# docking-control.net
KiCad netlist of a schematic drawn in Altium Designer
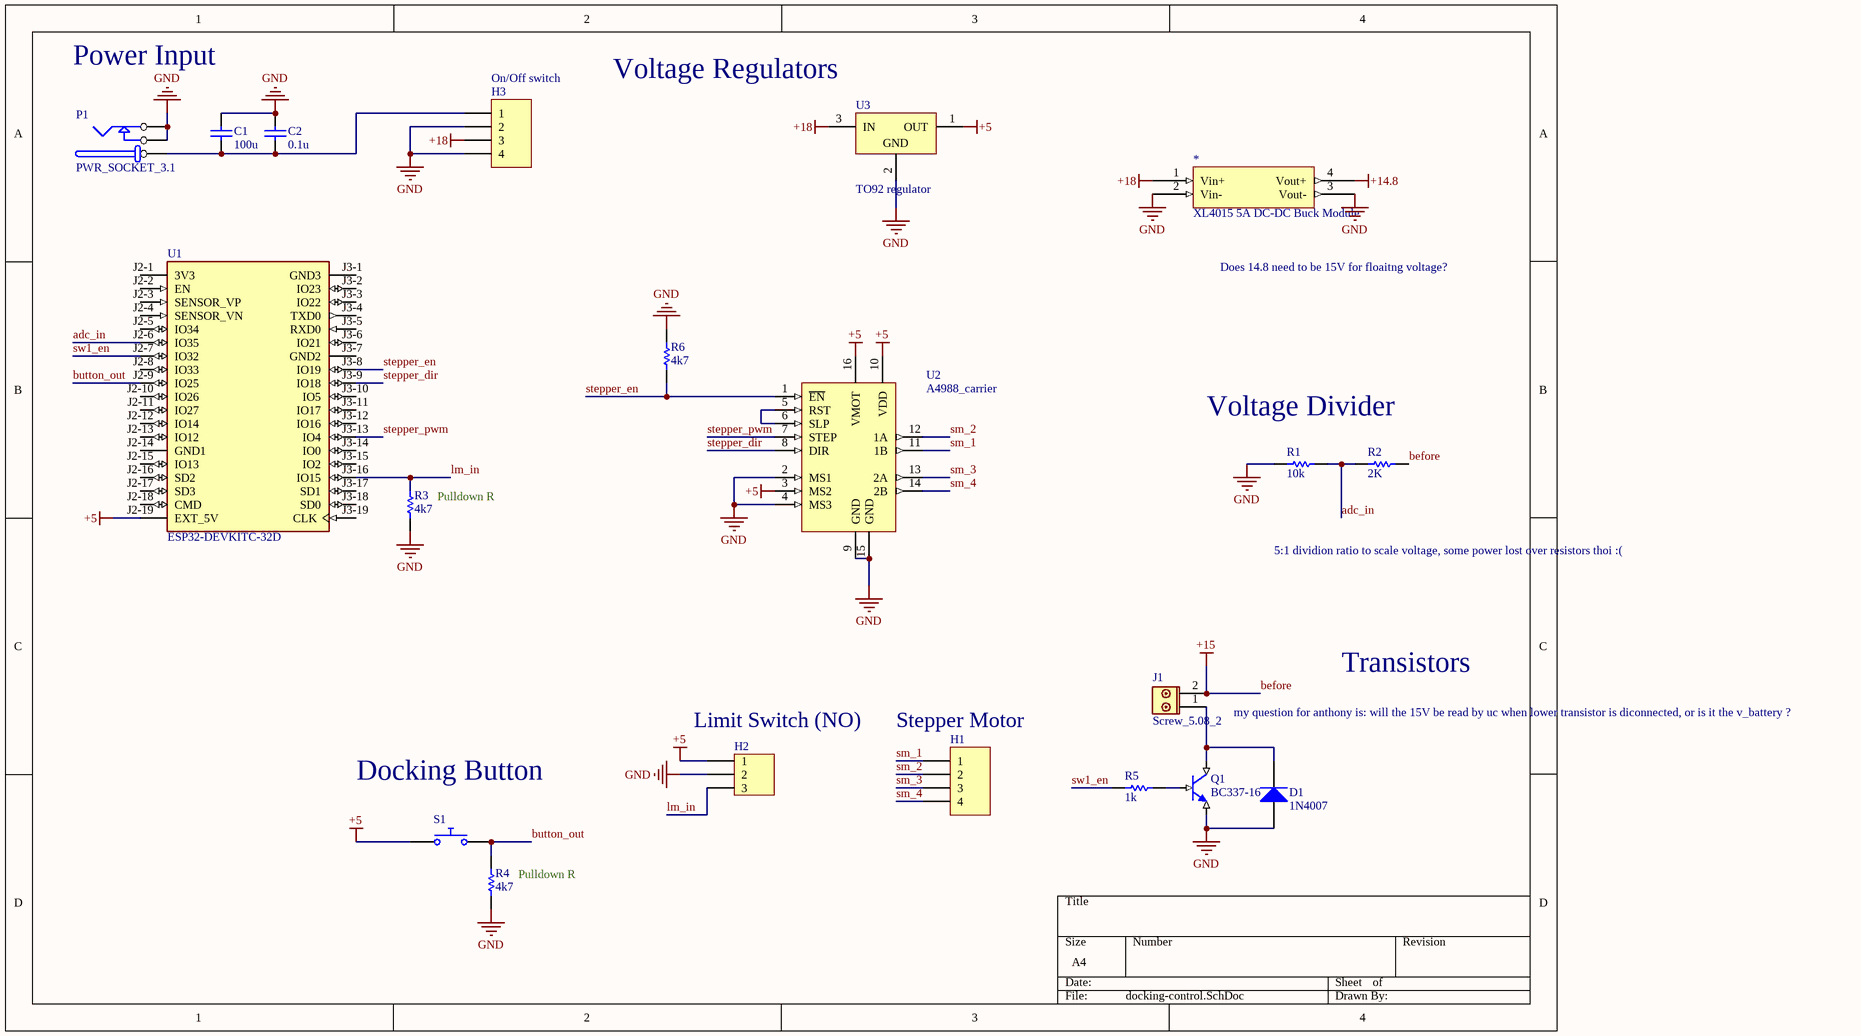
[diagram p0: docking-control.SchDoc]

(export (version "E")
  (design (tool "Eeschema 10.0.6"))
  (components
    (comp (ref "*")
      (value "XL4015 5A DC-DC Buck Module")
      (footprint "XL4015 5A DC-DC Buck Module-Footprint-1")
      (libsource (lib "Massey University") (part "XL4015 5A DC-DC Buck Module-Symbol-1"))
    )
    (comp (ref "C1")
      (value "100u")
      (footprint "RAD200_A")
      (description "Capacitor")
      (fields
        (field (name "MANUFACTURER") "Generic Components")
        (field (name "Comment") "Cap")
        (field (name "PUBLISHER") "Altium Hobart Technology Centre")
      )
      (libsource (lib "massey_libs") (part "Cap"))
    )
    (comp (ref "C2")
      (value "0.1u")
      (footprint "RAD200_A")
      (description "Capacitor")
      (fields
        (field (name "MANUFACTURER") "Generic Components")
        (field (name "Comment") "Cap")
        (field (name "PUBLISHER") "Altium Hobart Technology Centre")
      )
      (libsource (lib "massey_libs") (part "Cap"))
    )
    (comp (ref "D1")
      (value "1N4007")
      (footprint "DIODE400")
      (description "1.0 Ampere General Purpose Rectifier")
      (fields
        (field (name "MANUFACTURER") "Fairchild Semiconductor")
        (field (name "PUBLISHER") "Altium Hobart Technology Centre")
      )
      (libsource (lib "massey_libs") (part "1N4007"))
    )
    (comp (ref "H1")
      (value "Header 4")
      (footprint "HDR1X4")
      (description "Header, 4-Pin")
      (fields (field (name "MANUFACTURER") "Generic Components"))
      (libsource (lib "massey_libs") (part "Header 4"))
    )
    (comp (ref "H2")
      (value "Header 3")
      (footprint "HDR1X3")
      (description "Header, 3-Pin")
      (fields (field (name "MANUFACTURER") "Generic Components"))
      (libsource (lib "massey_libs") (part "Header 3"))
    )
    (comp (ref "H3")
      (value "Header 4")
      (footprint "HDR1X4")
      (description "Header, 4-Pin")
      (fields (field (name "MANUFACTURER") "Generic Components"))
      (libsource (lib "massey_libs") (part "Header 4"))
    )
    (comp (ref "J1")
      (value "Screw_5.08_2")
      (footprint "ScrewTerm_2.54_2")
      (description "2 way screw terminal connector")
      (libsource (lib "massey_libs") (part "Screw_5.08_2"))
    )
    (comp (ref "P1")
      (value "PWR_SOCKET_3.1")
      (footprint "PWR_SOCKET_3.1")
      (libsource (lib "massey_libs") (part "PWR_SOCKET_3.1"))
    )
    (comp (ref "Q1")
      (value "BC337-16")
      (footprint "TO-92A")
      (description "NPN BJT")
      (libsource (lib "massey_libs") (part "BC337-16"))
    )
    (comp (ref "R1")
      (value "10k")
      (description "Resistor")
      (libsource (lib "Simulation Generic Components") (part "Resistor"))
    )
    (comp (ref "R2")
      (value "2K")
      (description "Resistor")
      (libsource (lib "Simulation Generic Components") (part "Resistor"))
    )
    (comp (ref "R3")
      (value "4k7")
      (description "Resistor")
      (libsource (lib "Simulation Generic Components") (part "Resistor"))
    )
    (comp (ref "R4")
      (value "4k7")
      (description "Resistor")
      (libsource (lib "Simulation Generic Components") (part "Resistor"))
    )
    (comp (ref "R5")
      (value "1k")
      (footprint "AXIAL400")
      (description "Resistor")
      (fields
        (field (name "MANUFACTURER") "Generic Components")
        (field (name "Comment") "Res")
        (field (name "PUBLISHER") "Altium Hobart Technology Centre")
      )
      (libsource (lib "massey_libs") (part "Res"))
    )
    (comp (ref "R6")
      (value "4k7")
      (footprint "AXIAL400")
      (description "Resistor")
      (fields
        (field (name "MANUFACTURER") "Generic Components")
        (field (name "Comment") "Res")
        (field (name "PUBLISHER") "Altium Hobart Technology Centre")
      )
      (libsource (lib "massey_libs") (part "Res"))
    )
    (comp (ref "S1")
      (value "Push Button Normally Opened")
      (libsource (lib "Simulation Generic Components") (part "Push Button NO"))
    )
    (comp (ref "U1")
      (value "ESP32-DEVKITC-32D")
      (footprint "MODULE_ESP32-DEVKITC-32D")
      (description "WiFi Development Tools (802.11) ESP32 General Development Kit, ESP32-WROOM-32D on the board")
      (fields (field (name "MF") "Espressif Systems"))
      (libsource (lib "ESP32-DEVKITC-32D") (part "ESP32-DEVKITC-32D"))
    )
    (comp (ref "U2")
      (value "A4988_carrier")
      (footprint "DIP-16x500")
      (description "Carrier pcb for A4988 stepper driver")
      (libsource (lib "massey_libs") (part "A4988_carrier"))
    )
    (comp (ref "U3")
      (value "TO92 regulator")
      (footprint "TO-92A")
      (description "Positive Regulator  3.3V, 5V")
      (fields (field (name "PUBLISHER") "Altium Limited"))
      (libsource (lib "massey_libs") (part "REG_TO92"))
    )
  )
  (nets
    (net (code "1") (name "+5") (class "Default")
      (node (ref "H2") (pin "1") (pinfunction "1_1") (pintype "passive"))
      (node (ref "S1") (pin "1") (pinfunction "1_1") (pintype "passive"))
      (node (ref "U1") (pin "J2-19") (pinfunction "EXT_5V_J2-19") (pintype "power_in"))
      (node (ref "U2") (pin "10") (pinfunction "VDD_10") (pintype "power_in"))
      (node (ref "U2") (pin "16") (pinfunction "VMOT_16") (pintype "power_in"))
      (node (ref "U2") (pin "3") (pinfunction "MS2_3") (pintype "input"))
      (node (ref "U3") (pin "1") (pinfunction "OUT_1") (pintype "power_in"))
    )
    (net (code "2") (name "+14.8") (class "Default")
      (node (ref "*") (pin "4") (pinfunction "Vout+_4") (pintype "output"))
    )
    (net (code "3") (name "+15") (class "Default")
      (node (ref "J1") (pin "2") (pinfunction "2_2") (pintype "passive"))
      (node (ref "R2") (pin "1") (pinfunction "1_1") (pintype "passive"))
    )
    (net (code "4") (name "+18") (class "Default")
      (node (ref "*") (pin "1") (pinfunction "Vin+_1") (pintype "input"))
      (node (ref "H3") (pin "3") (pinfunction "3_3") (pintype "passive"))
      (node (ref "U3") (pin "3") (pinfunction "IN_3") (pintype "power_in"))
    )
    (net (code "5") (name "/adc_in") (class "Default")
      (node (ref "R1") (pin "1") (pinfunction "1_1") (pintype "passive"))
      (node (ref "R2") (pin "2") (pinfunction "2_2") (pintype "passive"))
      (node (ref "U1") (pin "J2-6") (pinfunction "IO35_J2-6") (pintype "bidirectional"))
    )
    (net (code "6") (name "/button_out") (class "Default")
      (node (ref "R4") (pin "1") (pinfunction "1_1") (pintype "passive"))
      (node (ref "S1") (pin "2") (pinfunction "2_2") (pintype "passive"))
      (node (ref "U1") (pin "J2-9") (pinfunction "IO25_J2-9") (pintype "bidirectional"))
    )
    (net (code "7") (name "/lm_in") (class "Default")
      (node (ref "H2") (pin "3") (pinfunction "3_3") (pintype "passive"))
      (node (ref "R3") (pin "1") (pinfunction "1_1") (pintype "passive"))
      (node (ref "U1") (pin "J3-16") (pinfunction "IO15_J3-16") (pintype "bidirectional"))
    )
    (net (code "8") (name "/sm_1") (class "Default")
      (node (ref "H1") (pin "1") (pinfunction "1_1") (pintype "passive"))
      (node (ref "U2") (pin "11") (pinfunction "1B_11") (pintype "output"))
    )
    (net (code "9") (name "/sm_2") (class "Default")
      (node (ref "H1") (pin "2") (pinfunction "2_2") (pintype "passive"))
      (node (ref "U2") (pin "12") (pinfunction "1A_12") (pintype "output"))
    )
    (net (code "10") (name "/sm_3") (class "Default")
      (node (ref "H1") (pin "3") (pinfunction "3_3") (pintype "passive"))
      (node (ref "U2") (pin "13") (pinfunction "2A_13") (pintype "output"))
    )
    (net (code "11") (name "/sm_4") (class "Default")
      (node (ref "H1") (pin "4") (pinfunction "4_4") (pintype "passive"))
      (node (ref "U2") (pin "14") (pinfunction "2B_14") (pintype "output"))
    )
    (net (code "12") (name "/stepper_dir") (class "Default")
      (node (ref "U1") (pin "J3-9") (pinfunction "IO18_J3-9") (pintype "bidirectional"))
      (node (ref "U2") (pin "8") (pinfunction "DIR_8") (pintype "input"))
    )
    (net (code "13") (name "/stepper_en") (class "Default")
      (node (ref "R6") (pin "1") (pinfunction "1_1") (pintype "passive"))
      (node (ref "U1") (pin "J3-8") (pinfunction "IO19_J3-8") (pintype "bidirectional"))
      (node (ref "U2") (pin "1") (pinfunction "~{EN}_1") (pintype "input"))
    )
    (net (code "14") (name "/stepper_pwm") (class "Default")
      (node (ref "U1") (pin "J3-13") (pinfunction "IO4_J3-13") (pintype "bidirectional"))
      (node (ref "U2") (pin "7") (pinfunction "STEP_7") (pintype "input"))
    )
    (net (code "15") (name "/sw1_en") (class "Default")
      (node (ref "R5") (pin "1") (pinfunction "1_1") (pintype "passive"))
      (node (ref "U1") (pin "J2-7") (pinfunction "IO32_J2-7") (pintype "bidirectional"))
    )
    (net (code "16") (name "GND") (class "Default")
      (node (ref "*") (pin "2") (pinfunction "Vin-_2") (pintype "input"))
      (node (ref "*") (pin "3") (pinfunction "Vout-_3") (pintype "output"))
      (node (ref "C1") (pin "2") (pinfunction "2_2") (pintype "passive"))
      (node (ref "C2") (pin "2") (pinfunction "2_2") (pintype "passive"))
      (node (ref "D1") (pin "1") (pinfunction "A_1") (pintype "passive"))
      (node (ref "H2") (pin "2") (pinfunction "2_2") (pintype "passive"))
      (node (ref "H3") (pin "2") (pinfunction "2_2") (pintype "passive"))
      (node (ref "H3") (pin "4") (pinfunction "4_4") (pintype "passive"))
      (node (ref "P1") (pin "2") (pinfunction "B_2") (pintype "passive"))
      (node (ref "P1") (pin "3") (pinfunction "C_3") (pintype "passive"))
      (node (ref "Q1") (pin "3") (pinfunction "E_3") (pintype "input"))
      (node (ref "R1") (pin "2") (pinfunction "2_2") (pintype "passive"))
      (node (ref "R3") (pin "2") (pinfunction "2_2") (pintype "passive"))
      (node (ref "R4") (pin "2") (pinfunction "2_2") (pintype "passive"))
      (node (ref "R6") (pin "2") (pinfunction "2_2") (pintype "passive"))
      (node (ref "U2") (pin "15") (pinfunction "GND_15") (pintype "power_in"))
      (node (ref "U2") (pin "2") (pinfunction "MS1_2") (pintype "input"))
      (node (ref "U2") (pin "4") (pinfunction "MS3_4") (pintype "input"))
      (node (ref "U2") (pin "9") (pinfunction "GND_9") (pintype "power_in"))
      (node (ref "U3") (pin "2") (pinfunction "GND_2") (pintype "power_in"))
    )
    (net (code "17") (name "Net-(D1-K)") (class "Default")
      (node (ref "D1") (pin "2") (pinfunction "K_2") (pintype "passive"))
      (node (ref "J1") (pin "1") (pinfunction "1_1") (pintype "passive"))
      (node (ref "Q1") (pin "1") (pinfunction "C_1") (pintype "input"))
    )
    (net (code "18") (name "Net-(P1-A)") (class "Default")
      (node (ref "C1") (pin "1") (pinfunction "1_1") (pintype "passive"))
      (node (ref "C2") (pin "1") (pinfunction "1_1") (pintype "passive"))
      (node (ref "H3") (pin "1") (pinfunction "1_1") (pintype "passive"))
      (node (ref "P1") (pin "1") (pinfunction "A_1") (pintype "passive"))
    )
    (net (code "19") (name "Net-(Q1-B)") (class "Default")
      (node (ref "Q1") (pin "2") (pinfunction "B_2") (pintype "input"))
      (node (ref "R5") (pin "2") (pinfunction "2_2") (pintype "passive"))
    )
    (net (code "20") (name "Net-(U2-RST)") (class "Default")
      (node (ref "U2") (pin "5") (pinfunction "RST_5") (pintype "input"))
      (node (ref "U2") (pin "6") (pinfunction "SLP_6") (pintype "input"))
    )
    (net (code "21") (name "unconnected-(U1-3V3-PadJ2-1)") (class "Default")
      (node (ref "U1") (pin "J2-1") (pinfunction "3V3_J2-1") (pintype "power_in"))
    )
    (net (code "22") (name "unconnected-(U1-CLK-PadJ3-19)") (class "Default")
      (node (ref "U1") (pin "J3-19") (pinfunction "CLK_J3-19") (pintype "input"))
    )
    (net (code "23") (name "unconnected-(U1-CMD-PadJ2-18)") (class "Default")
      (node (ref "U1") (pin "J2-18") (pinfunction "CMD_J2-18") (pintype "bidirectional"))
    )
    (net (code "24") (name "unconnected-(U1-EN-PadJ2-2)") (class "Default")
      (node (ref "U1") (pin "J2-2") (pinfunction "EN_J2-2") (pintype "input"))
    )
    (net (code "25") (name "unconnected-(U1-GND1-PadJ2-14)") (class "Default")
      (node (ref "U1") (pin "J2-14") (pinfunction "GND1_J2-14") (pintype "power_in"))
    )
    (net (code "26") (name "unconnected-(U1-GND2-PadJ3-7)") (class "Default")
      (node (ref "U1") (pin "J3-7") (pinfunction "GND2_J3-7") (pintype "power_in"))
    )
    (net (code "27") (name "unconnected-(U1-GND3-PadJ3-1)") (class "Default")
      (node (ref "U1") (pin "J3-1") (pinfunction "GND3_J3-1") (pintype "power_in"))
    )
    (net (code "28") (name "unconnected-(U1-IO0-PadJ3-14)") (class "Default")
      (node (ref "U1") (pin "J3-14") (pinfunction "IO0_J3-14") (pintype "bidirectional"))
    )
    (net (code "29") (name "unconnected-(U1-IO2-PadJ3-15)") (class "Default")
      (node (ref "U1") (pin "J3-15") (pinfunction "IO2_J3-15") (pintype "bidirectional"))
    )
    (net (code "30") (name "unconnected-(U1-IO5-PadJ3-10)") (class "Default")
      (node (ref "U1") (pin "J3-10") (pinfunction "IO5_J3-10") (pintype "bidirectional"))
    )
    (net (code "31") (name "unconnected-(U1-IO12-PadJ2-13)") (class "Default")
      (node (ref "U1") (pin "J2-13") (pinfunction "IO12_J2-13") (pintype "bidirectional"))
    )
    (net (code "32") (name "unconnected-(U1-IO13-PadJ2-15)") (class "Default")
      (node (ref "U1") (pin "J2-15") (pinfunction "IO13_J2-15") (pintype "bidirectional"))
    )
    (net (code "33") (name "unconnected-(U1-IO14-PadJ2-12)") (class "Default")
      (node (ref "U1") (pin "J2-12") (pinfunction "IO14_J2-12") (pintype "bidirectional"))
    )
    (net (code "34") (name "unconnected-(U1-IO16-PadJ3-12)") (class "Default")
      (node (ref "U1") (pin "J3-12") (pinfunction "IO16_J3-12") (pintype "bidirectional"))
    )
    (net (code "35") (name "unconnected-(U1-IO17-PadJ3-11)") (class "Default")
      (node (ref "U1") (pin "J3-11") (pinfunction "IO17_J3-11") (pintype "bidirectional"))
    )
    (net (code "36") (name "unconnected-(U1-IO21-PadJ3-6)") (class "Default")
      (node (ref "U1") (pin "J3-6") (pinfunction "IO21_J3-6") (pintype "bidirectional"))
    )
    (net (code "37") (name "unconnected-(U1-IO22-PadJ3-3)") (class "Default")
      (node (ref "U1") (pin "J3-3") (pinfunction "IO22_J3-3") (pintype "bidirectional"))
    )
    (net (code "38") (name "unconnected-(U1-IO23-PadJ3-2)") (class "Default")
      (node (ref "U1") (pin "J3-2") (pinfunction "IO23_J3-2") (pintype "bidirectional"))
    )
    (net (code "39") (name "unconnected-(U1-IO26-PadJ2-10)") (class "Default")
      (node (ref "U1") (pin "J2-10") (pinfunction "IO26_J2-10") (pintype "bidirectional"))
    )
    (net (code "40") (name "unconnected-(U1-IO27-PadJ2-11)") (class "Default")
      (node (ref "U1") (pin "J2-11") (pinfunction "IO27_J2-11") (pintype "bidirectional"))
    )
    (net (code "41") (name "unconnected-(U1-IO33-PadJ2-8)") (class "Default")
      (node (ref "U1") (pin "J2-8") (pinfunction "IO33_J2-8") (pintype "bidirectional"))
    )
    (net (code "42") (name "unconnected-(U1-IO34-PadJ2-5)") (class "Default")
      (node (ref "U1") (pin "J2-5") (pinfunction "IO34_J2-5") (pintype "bidirectional"))
    )
    (net (code "43") (name "unconnected-(U1-RXD0-PadJ3-5)") (class "Default")
      (node (ref "U1") (pin "J3-5") (pinfunction "RXD0_J3-5") (pintype "input"))
    )
    (net (code "44") (name "unconnected-(U1-SD0-PadJ3-18)") (class "Default")
      (node (ref "U1") (pin "J3-18") (pinfunction "SD0_J3-18") (pintype "bidirectional"))
    )
    (net (code "45") (name "unconnected-(U1-SD1-PadJ3-17)") (class "Default")
      (node (ref "U1") (pin "J3-17") (pinfunction "SD1_J3-17") (pintype "bidirectional"))
    )
    (net (code "46") (name "unconnected-(U1-SD2-PadJ2-16)") (class "Default")
      (node (ref "U1") (pin "J2-16") (pinfunction "SD2_J2-16") (pintype "bidirectional"))
    )
    (net (code "47") (name "unconnected-(U1-SD3-PadJ2-17)") (class "Default")
      (node (ref "U1") (pin "J2-17") (pinfunction "SD3_J2-17") (pintype "bidirectional"))
    )
    (net (code "48") (name "unconnected-(U1-SENSOR_VN-PadJ2-4)") (class "Default")
      (node (ref "U1") (pin "J2-4") (pinfunction "SENSOR_VN_J2-4") (pintype "input"))
    )
    (net (code "49") (name "unconnected-(U1-SENSOR_VP-PadJ2-3)") (class "Default")
      (node (ref "U1") (pin "J2-3") (pinfunction "SENSOR_VP_J2-3") (pintype "input"))
    )
    (net (code "50") (name "unconnected-(U1-TXD0-PadJ3-4)") (class "Default")
      (node (ref "U1") (pin "J3-4") (pinfunction "TXD0_J3-4") (pintype "output"))
    )
  )
)
